# trinket_power_sensing_backback.net
KiCad netlist of a schematic drawn in EAGLE
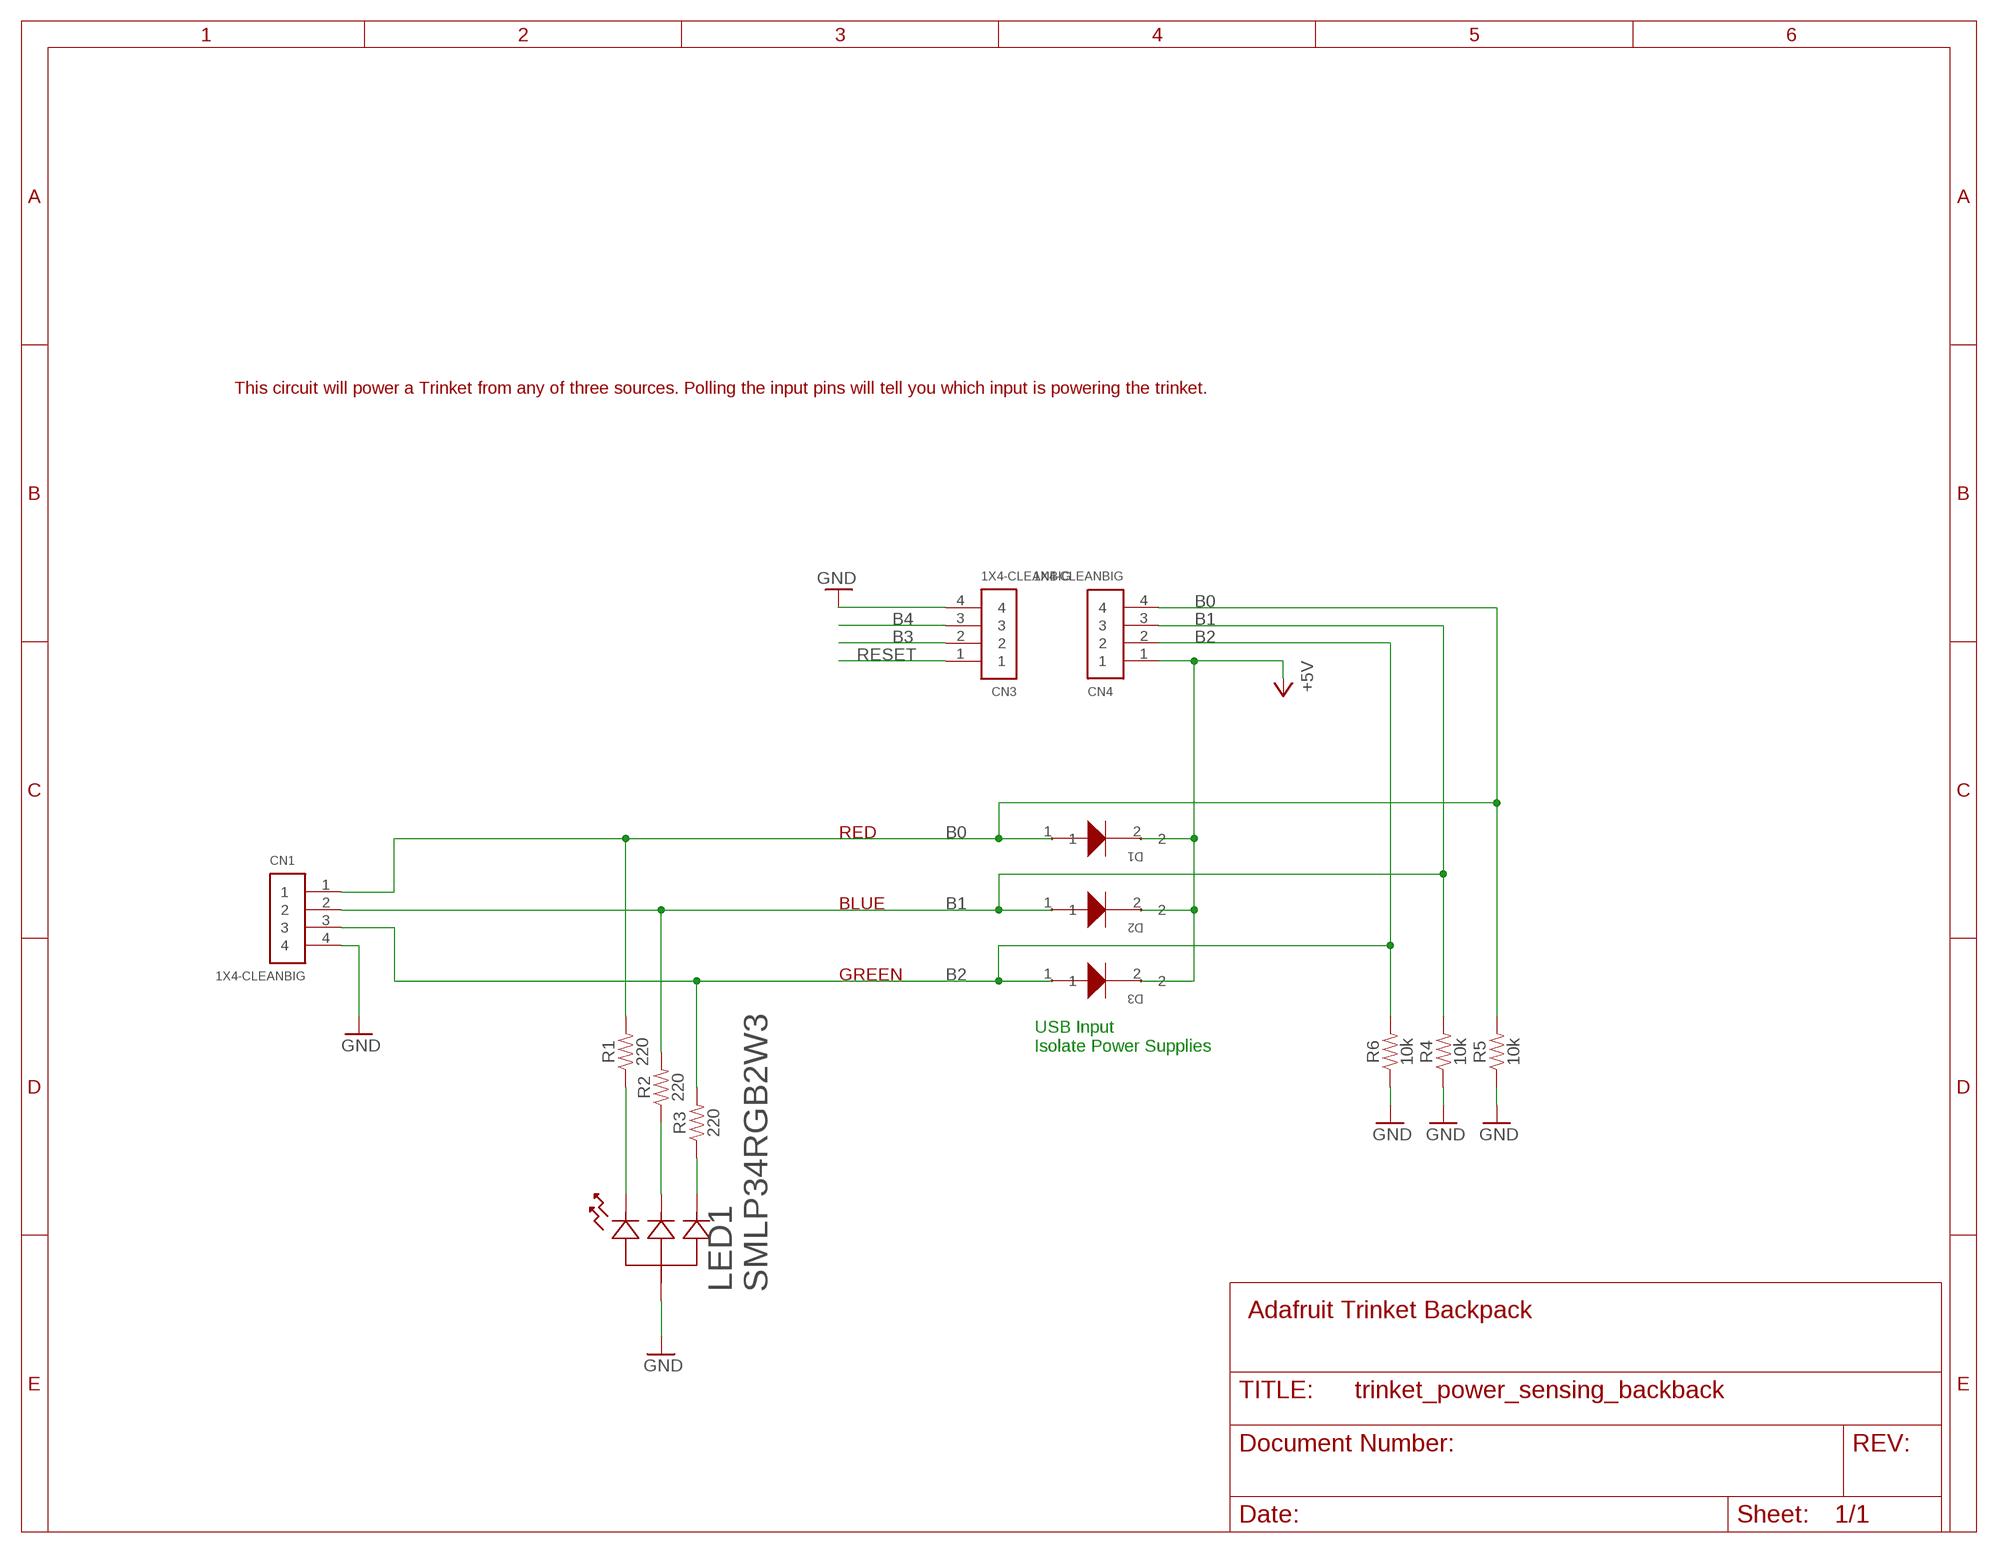
[diagram p0: schematic, sheet 1]

(export (version "E")
  (design (tool "Eeschema 10.0.6"))
  (components
    (comp (ref "CN1")
      (value "1X4-CLEANBIG")
      (footprint "eagle-import:1X04-CLEANBIG")
      (libsource (lib "eagle-import") (part "1X4-CLEANBIG"))
    )
    (comp (ref "CN3")
      (value "1X4-CLEANBIG")
      (footprint "eagle-import:1X04-CLEANBIG")
      (libsource (lib "eagle-import") (part "1X4-CLEANBIG"))
    )
    (comp (ref "CN4")
      (value "1X4-CLEANBIG")
      (footprint "eagle-import:1X04-CLEANBIG")
      (libsource (lib "eagle-import") (part "1X4-CLEANBIG"))
    )
    (comp (ref "D1")
      (value "CMF04(TE12L,Q,M)")
      (footprint "eagle-import:M-FLAT_TOS")
      (fields (field (name "COPYRIGHT") "Copyright (C) 2018 Accelerated Designs. All rights reserved"))
      (libsource (lib "eagle-import") (part "CMF04(TE12L,Q,M)"))
    )
    (comp (ref "D2")
      (value "CMF04(TE12L,Q,M)")
      (footprint "eagle-import:M-FLAT_TOS")
      (fields (field (name "COPYRIGHT") "Copyright (C) 2018 Accelerated Designs. All rights reserved"))
      (libsource (lib "eagle-import") (part "CMF04(TE12L,Q,M)"))
    )
    (comp (ref "D3")
      (value "CMF04(TE12L,Q,M)")
      (footprint "eagle-import:M-FLAT_TOS")
      (fields (field (name "COPYRIGHT") "Copyright (C) 2018 Accelerated Designs. All rights reserved"))
      (libsource (lib "eagle-import") (part "CMF04(TE12L,Q,M)"))
    )
    (comp (ref "LED1")
      (value "SMLP34RGB2W3")
      (footprint "eagle-import:LED_SML-P24M_ROM")
      (fields (field (name "COPYRIGHT") "Copyright (C) 2018 Accelerated Designs. All rights reserved"))
      (libsource (lib "eagle-import") (part "SMLP34RGB2W3"))
    )
    (comp (ref "R1")
      (value "220")
      (footprint "eagle-import:0603")
      (libsource (lib "eagle-import") (part "220OHM-0603-1/10W-1%"))
    )
    (comp (ref "R2")
      (value "220")
      (footprint "eagle-import:0603")
      (libsource (lib "eagle-import") (part "220OHM-0603-1/10W-1%"))
    )
    (comp (ref "R3")
      (value "220")
      (footprint "eagle-import:0603")
      (libsource (lib "eagle-import") (part "220OHM-0603-1/10W-1%"))
    )
    (comp (ref "R4")
      (value "10k")
      (footprint "eagle-import:0603")
      (libsource (lib "eagle-import") (part "220OHM-0603-1/10W-1%"))
    )
    (comp (ref "R5")
      (value "10k")
      (footprint "eagle-import:0603")
      (libsource (lib "eagle-import") (part "220OHM-0603-1/10W-1%"))
    )
    (comp (ref "R6")
      (value "10k")
      (footprint "eagle-import:0603")
      (libsource (lib "eagle-import") (part "220OHM-0603-1/10W-1%"))
    )
  )
  (nets
    (net (code "1") (name "+5V") (class "Default")
      (node (ref "CN4") (pin "1") (pinfunction "1_1") (pintype "bidirectional"))
      (node (ref "D1") (pin "2") (pinfunction "2_2") (pintype "passive"))
      (node (ref "D2") (pin "2") (pinfunction "2_2") (pintype "passive"))
      (node (ref "D3") (pin "2") (pinfunction "2_2") (pintype "passive"))
    )
    (net (code "2") (name "/B0") (class "Default")
      (node (ref "CN1") (pin "1") (pinfunction "1_1") (pintype "bidirectional"))
      (node (ref "CN4") (pin "4") (pinfunction "4_4") (pintype "bidirectional"))
      (node (ref "D1") (pin "1") (pinfunction "1_1") (pintype "passive"))
      (node (ref "R1") (pin "2") (pinfunction "2_2") (pintype "passive"))
      (node (ref "R5") (pin "2") (pinfunction "2_2") (pintype "passive"))
    )
    (net (code "3") (name "/B1") (class "Default")
      (node (ref "CN1") (pin "2") (pinfunction "2_2") (pintype "bidirectional"))
      (node (ref "CN4") (pin "3") (pinfunction "3_3") (pintype "bidirectional"))
      (node (ref "D2") (pin "1") (pinfunction "1_1") (pintype "passive"))
      (node (ref "R2") (pin "2") (pinfunction "2_2") (pintype "passive"))
      (node (ref "R4") (pin "2") (pinfunction "2_2") (pintype "passive"))
    )
    (net (code "4") (name "/B2") (class "Default")
      (node (ref "CN1") (pin "3") (pinfunction "3_3") (pintype "bidirectional"))
      (node (ref "CN4") (pin "2") (pinfunction "2_2") (pintype "bidirectional"))
      (node (ref "D3") (pin "1") (pinfunction "1_1") (pintype "passive"))
      (node (ref "R3") (pin "2") (pinfunction "2_2") (pintype "passive"))
      (node (ref "R6") (pin "2") (pinfunction "2_2") (pintype "passive"))
    )
    (net (code "5") (name "/B3") (class "Default")
      (node (ref "CN3") (pin "2") (pinfunction "2_2") (pintype "bidirectional"))
    )
    (net (code "6") (name "/B4") (class "Default")
      (node (ref "CN3") (pin "3") (pinfunction "3_3") (pintype "bidirectional"))
    )
    (net (code "7") (name "/RESET") (class "Default")
      (node (ref "CN3") (pin "1") (pinfunction "1_1") (pintype "bidirectional"))
    )
    (net (code "8") (name "GND") (class "Default")
      (node (ref "CN1") (pin "4") (pinfunction "4_4") (pintype "bidirectional"))
      (node (ref "CN3") (pin "4") (pinfunction "4_4") (pintype "bidirectional"))
      (node (ref "LED1") (pin "1") (pinfunction "1_1") (pintype "passive"))
      (node (ref "R4") (pin "1") (pinfunction "1_1") (pintype "passive"))
      (node (ref "R5") (pin "1") (pinfunction "1_1") (pintype "passive"))
      (node (ref "R6") (pin "1") (pinfunction "1_1") (pintype "passive"))
    )
    (net (code "9") (name "Net-(LED1-Pad2)") (class "Default")
      (node (ref "LED1") (pin "2") (pinfunction "2_2") (pintype "passive"))
      (node (ref "R1") (pin "1") (pinfunction "1_1") (pintype "passive"))
    )
    (net (code "10") (name "Net-(LED1-Pad3)") (class "Default")
      (node (ref "LED1") (pin "3") (pinfunction "3_3") (pintype "passive"))
      (node (ref "R2") (pin "1") (pinfunction "1_1") (pintype "passive"))
    )
    (net (code "11") (name "Net-(LED1-Pad4)") (class "Default")
      (node (ref "LED1") (pin "4") (pinfunction "4_4") (pintype "passive"))
      (node (ref "R3") (pin "1") (pinfunction "1_1") (pintype "passive"))
    )
  )
)
